# Bottom_rev1.net
KiCad netlist of a schematic drawn in EAGLE
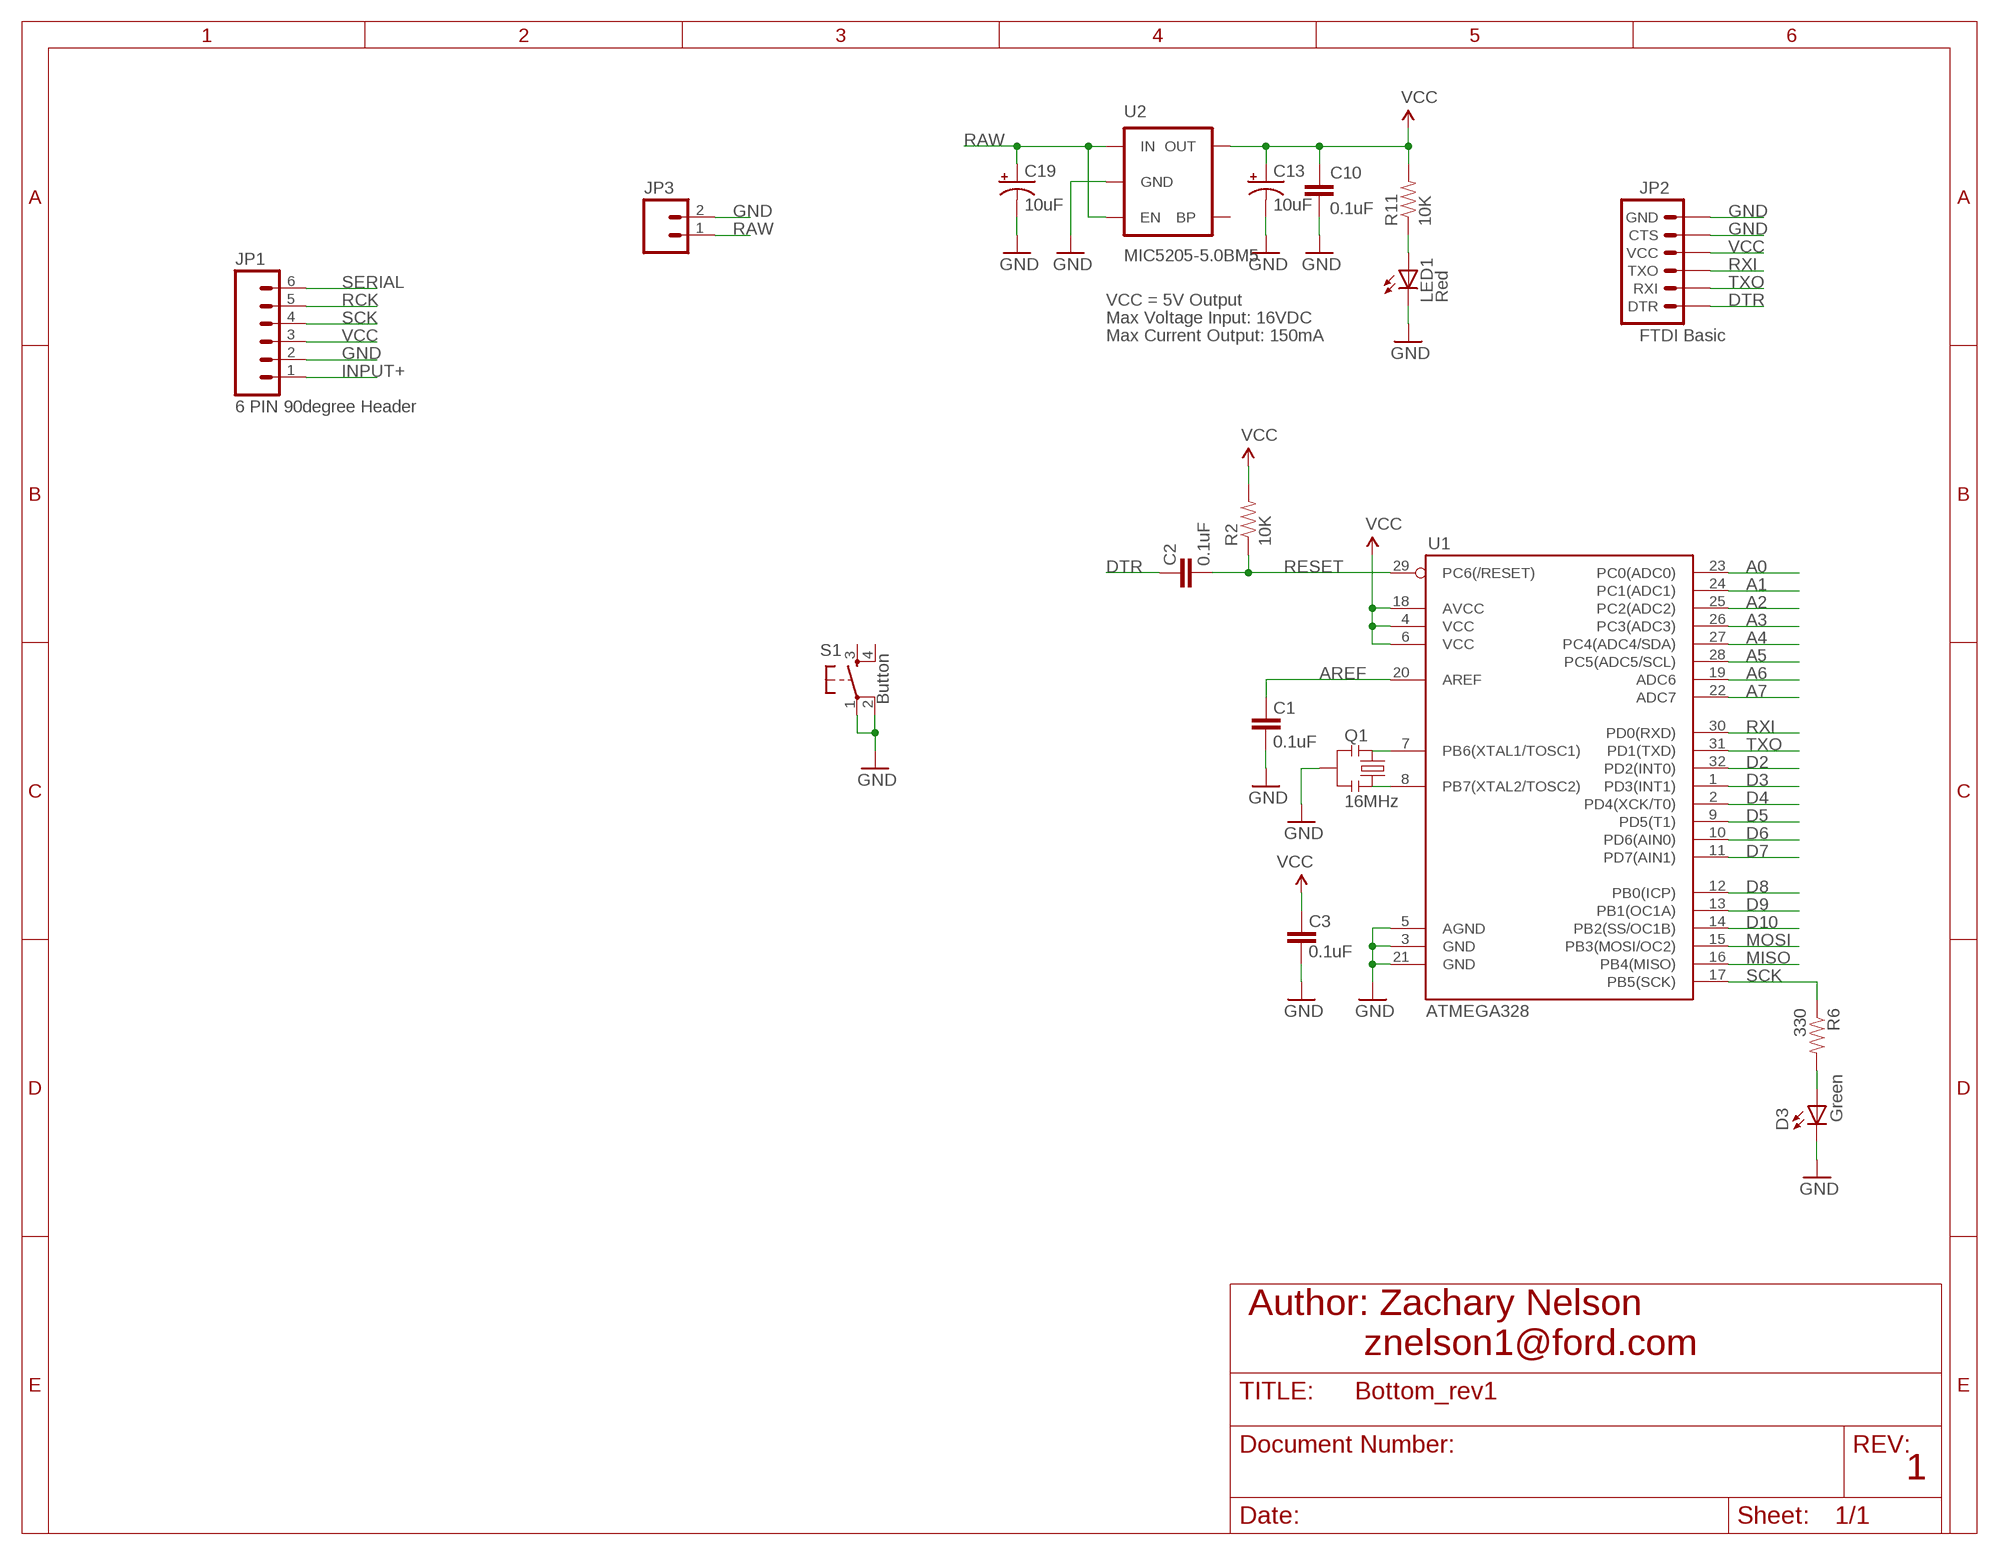
[diagram p0: schematic, sheet 1, part 1 of 2]
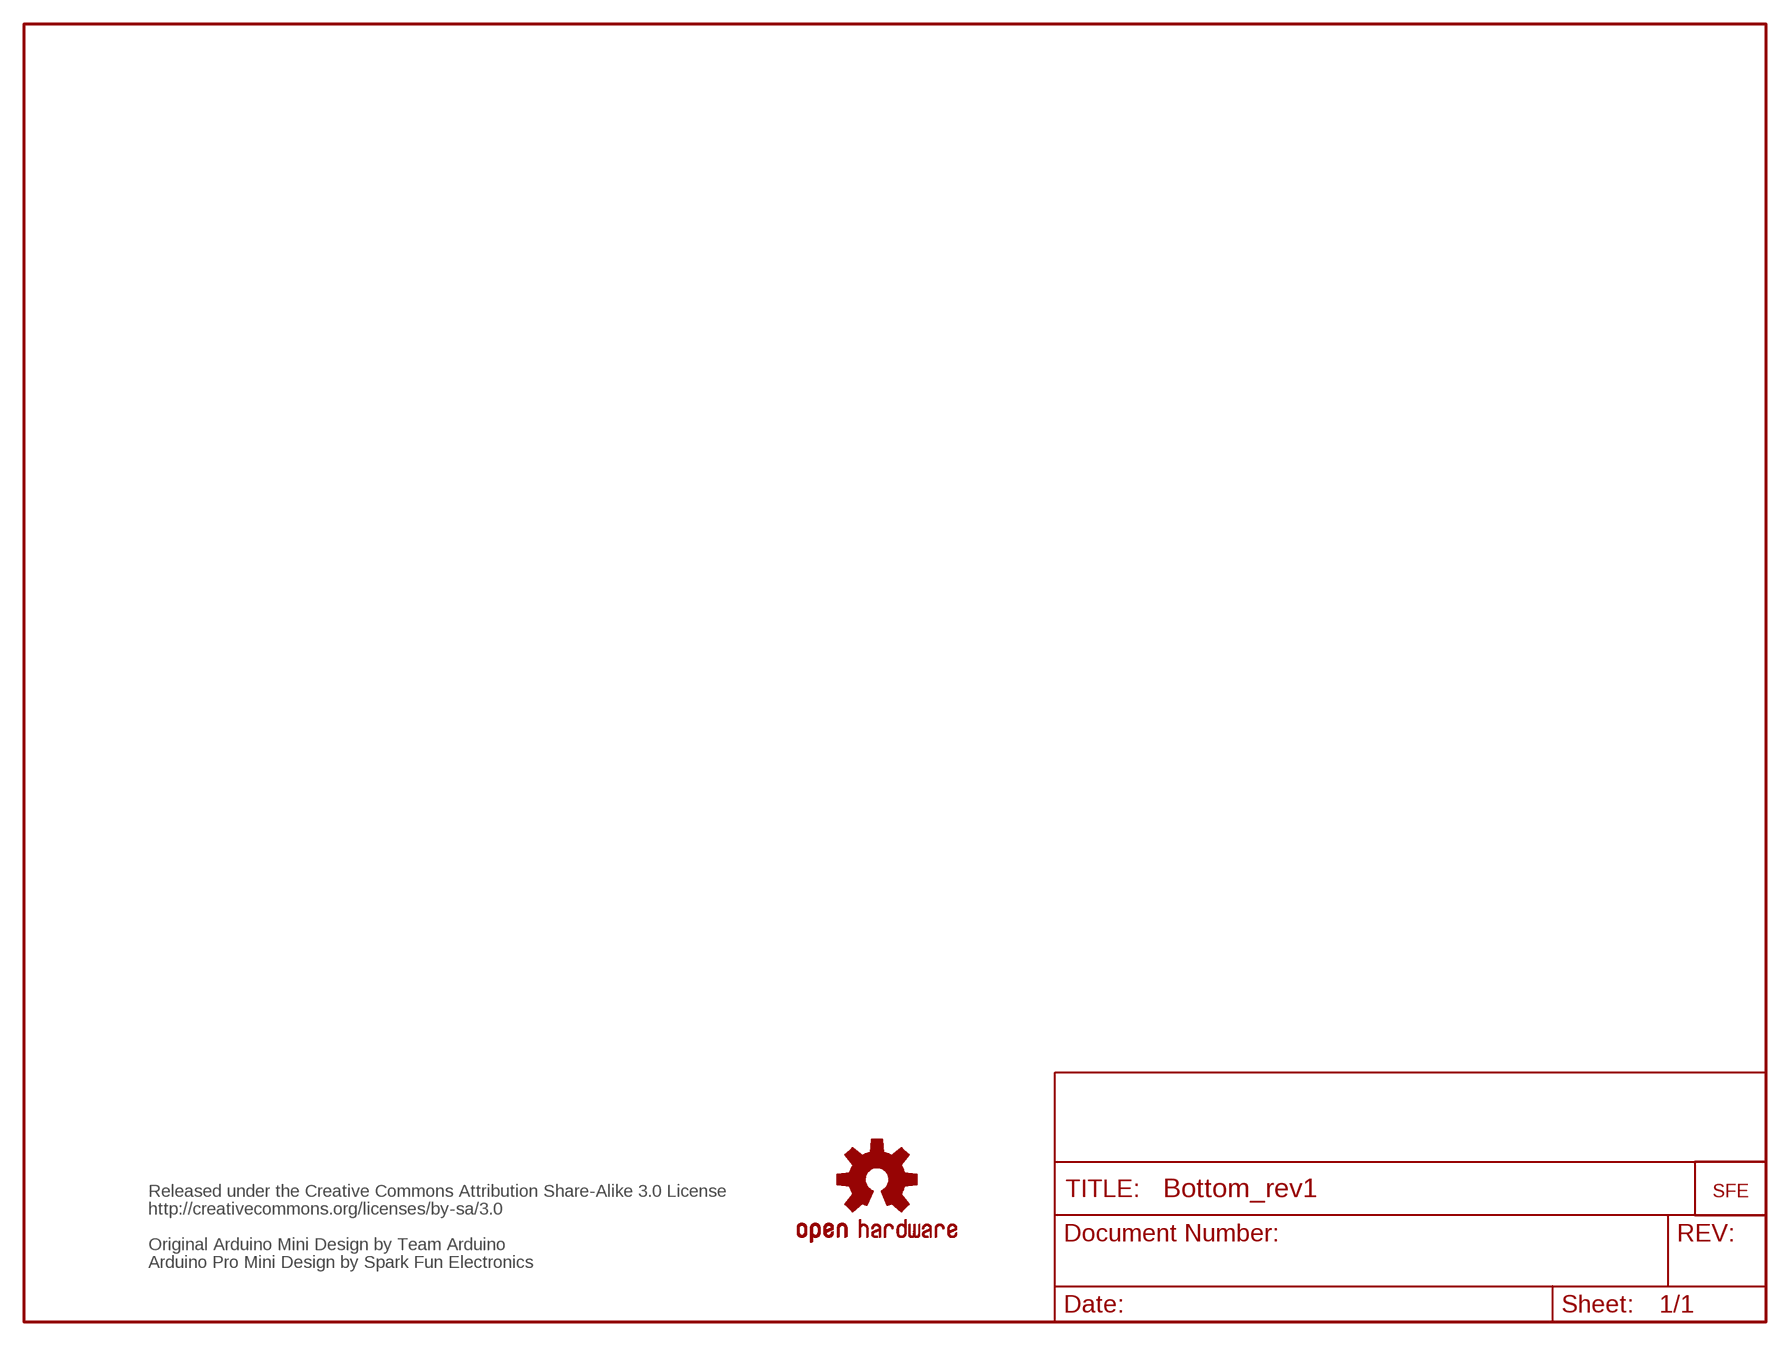
[diagram p1: schematic, sheet 1, part 2 of 2]

(export (version "E")
  (design (tool "Eeschema 10.0.6"))
  (components
    (comp (ref "C1")
      (value "0.1uF")
      (footprint "eagle-import:0402-CAP")
      (libsource (lib "eagle-import") (part "CAP0402-CAP"))
    )
    (comp (ref "C2")
      (value "0.1uF")
      (footprint "eagle-import:0402-CAP")
      (libsource (lib "eagle-import") (part "CAP0402-CAP"))
    )
    (comp (ref "C3")
      (value "0.1uF")
      (footprint "eagle-import:0402-CAP")
      (libsource (lib "eagle-import") (part "CAP0402-CAP"))
    )
    (comp (ref "C10")
      (value "0.1uF")
      (footprint "eagle-import:0402-CAP")
      (libsource (lib "eagle-import") (part "CAP0402-CAP"))
    )
    (comp (ref "C13")
      (value "10uF")
      (footprint "eagle-import:EIA3216")
      (libsource (lib "eagle-import") (part "CAP_POL1206"))
    )
    (comp (ref "C19")
      (value "10uF")
      (footprint "eagle-import:EIA3216")
      (libsource (lib "eagle-import") (part "CAP_POL1206"))
    )
    (comp (ref "D3")
      (value "Green")
      (footprint "eagle-import:LED-0603")
      (libsource (lib "eagle-import") (part "LED0603"))
    )
    (comp (ref "JP1")
      (value "6 PIN 90degree Header")
      (footprint "eagle-import:1X06_HOLES_ONLY")
      (libsource (lib "eagle-import") (part "M06POGOPIN_HOLES_ONLY"))
    )
    (comp (ref "JP2")
      (value "FTDI Basic")
      (footprint "eagle-import:1X06")
      (libsource (lib "eagle-import") (part "ARDUINO_SERIAL_PROGRAMPTH"))
    )
    (comp (ref "JP3")
      (value "M02POLAR")
      (footprint "eagle-import:MOLEX-1X2")
      (libsource (lib "eagle-import") (part "M02POLAR"))
    )
    (comp (ref "LED1")
      (value "Red")
      (footprint "eagle-import:LED-0603")
      (libsource (lib "eagle-import") (part "LED0603"))
    )
    (comp (ref "Q1")
      (value "16MHz")
      (footprint "eagle-import:RESONATOR-SMD")
      (libsource (lib "eagle-import") (part "RESONATORSMD"))
    )
    (comp (ref "R2")
      (value "10K")
      (footprint "eagle-import:0402-RES")
      (libsource (lib "eagle-import") (part "RESISTOR0402-RES"))
    )
    (comp (ref "R6")
      (value "330")
      (footprint "eagle-import:0402-RES")
      (libsource (lib "eagle-import") (part "RESISTOR0402-RES"))
    )
    (comp (ref "R11")
      (value "10K")
      (footprint "eagle-import:0402-RES")
      (libsource (lib "eagle-import") (part "RESISTOR0402-RES"))
    )
    (comp (ref "S1")
      (value "Button")
      (footprint "eagle-import:TACTILE_SWITCH_SMD")
      (libsource (lib "eagle-import") (part "TAC_SWITCHSMD"))
    )
    (comp (ref "U$3")
      (value "OSHW-LOGOS")
      (footprint "eagle-import:OSHW-LOGO-S")
      (libsource (lib "eagle-import") (part "OSHW-LOGOS"))
    )
    (comp (ref "U$11")
      (value "LOGO-SFENEW")
      (footprint "eagle-import:SFE-NEW-WEBLOGO")
      (libsource (lib "eagle-import") (part "LOGO-SFENEW"))
    )
    (comp (ref "U1")
      (value "ATMEGA328")
      (footprint "eagle-import:TQFP32-08")
      (libsource (lib "eagle-import") (part "ATMEGA168"))
    )
    (comp (ref "U2")
      (value "MIC5205-5.0BM5")
      (footprint "eagle-import:SOT23-5")
      (libsource (lib "eagle-import") (part "V_REG_LDOSMD"))
    )
  )
  (nets
    (net (code "1") (name "/A0") (class "Default")
      (node (ref "U1") (pin "23") (pinfunction "PC0(ADC0)_23") (pintype "bidirectional"))
    )
    (net (code "2") (name "/A1") (class "Default")
      (node (ref "U1") (pin "24") (pinfunction "PC1(ADC1)_24") (pintype "bidirectional"))
    )
    (net (code "3") (name "/A2") (class "Default")
      (node (ref "U1") (pin "25") (pinfunction "PC2(ADC2)_25") (pintype "bidirectional"))
    )
    (net (code "4") (name "/A3") (class "Default")
      (node (ref "U1") (pin "26") (pinfunction "PC3(ADC3)_26") (pintype "bidirectional"))
    )
    (net (code "5") (name "/A4") (class "Default")
      (node (ref "U1") (pin "27") (pinfunction "PC4(ADC4/SDA)_27") (pintype "bidirectional"))
    )
    (net (code "6") (name "/A5") (class "Default")
      (node (ref "U1") (pin "28") (pinfunction "PC5(ADC5/SCL)_28") (pintype "bidirectional"))
    )
    (net (code "7") (name "/A6") (class "Default")
      (node (ref "U1") (pin "19") (pinfunction "ADC6_19") (pintype "bidirectional"))
    )
    (net (code "8") (name "/A7") (class "Default")
      (node (ref "U1") (pin "22") (pinfunction "ADC7_22") (pintype "bidirectional"))
    )
    (net (code "9") (name "/AREF") (class "Default")
      (node (ref "C1") (pin "2") (pinfunction "2_2") (pintype "passive"))
      (node (ref "U1") (pin "20") (pinfunction "AREF_20") (pintype "bidirectional"))
    )
    (net (code "10") (name "/D2") (class "Default")
      (node (ref "U1") (pin "32") (pinfunction "PD2(INT0)_32") (pintype "bidirectional"))
    )
    (net (code "11") (name "/D3") (class "Default")
      (node (ref "U1") (pin "1") (pinfunction "PD3(INT1)_1") (pintype "bidirectional"))
    )
    (net (code "12") (name "/D4") (class "Default")
      (node (ref "U1") (pin "2") (pinfunction "PD4(XCK/T0)_2") (pintype "bidirectional"))
    )
    (net (code "13") (name "/D5") (class "Default")
      (node (ref "U1") (pin "9") (pinfunction "PD5(T1)_9") (pintype "bidirectional"))
    )
    (net (code "14") (name "/D6") (class "Default")
      (node (ref "U1") (pin "10") (pinfunction "PD6(AIN0)_10") (pintype "bidirectional"))
    )
    (net (code "15") (name "/D7") (class "Default")
      (node (ref "U1") (pin "11") (pinfunction "PD7(AIN1)_11") (pintype "bidirectional"))
    )
    (net (code "16") (name "/D8") (class "Default")
      (node (ref "U1") (pin "12") (pinfunction "PB0(ICP)_12") (pintype "bidirectional"))
    )
    (net (code "17") (name "/D9") (class "Default")
      (node (ref "U1") (pin "13") (pinfunction "PB1(OC1A)_13") (pintype "bidirectional"))
    )
    (net (code "18") (name "/D10") (class "Default")
      (node (ref "U1") (pin "14") (pinfunction "PB2(SS/OC1B)_14") (pintype "bidirectional"))
    )
    (net (code "19") (name "/DTR") (class "Default")
      (node (ref "C2") (pin "2") (pinfunction "2_2") (pintype "passive"))
      (node (ref "JP2") (pin "1") (pinfunction "DTR_1") (pintype "passive"))
    )
    (net (code "20") (name "/INPUT+") (class "Default")
      (node (ref "JP1") (pin "1") (pinfunction "1_1") (pintype "passive"))
    )
    (net (code "21") (name "/MISO") (class "Default")
      (node (ref "U1") (pin "16") (pinfunction "PB4(MISO)_16") (pintype "bidirectional"))
    )
    (net (code "22") (name "/MOSI") (class "Default")
      (node (ref "U1") (pin "15") (pinfunction "PB3(MOSI/OC2)_15") (pintype "bidirectional"))
    )
    (net (code "23") (name "/RAW") (class "Default")
      (node (ref "C19") (pin "A") (pinfunction "+_A") (pintype "passive"))
      (node (ref "JP3") (pin "1") (pinfunction "1_1") (pintype "passive"))
      (node (ref "U2") (pin "1") (pinfunction "IN_1") (pintype "input"))
      (node (ref "U2") (pin "3") (pinfunction "EN_3") (pintype "input"))
    )
    (net (code "24") (name "/RCK") (class "Default")
      (node (ref "JP1") (pin "5") (pinfunction "5_5") (pintype "passive"))
    )
    (net (code "25") (name "/RESET") (class "Default")
      (node (ref "C2") (pin "1") (pinfunction "1_1") (pintype "passive"))
      (node (ref "R2") (pin "1") (pinfunction "1_1") (pintype "passive"))
      (node (ref "U1") (pin "29") (pinfunction "PC6(/RESET)_29") (pintype "bidirectional"))
    )
    (net (code "26") (name "/RXI") (class "Default")
      (node (ref "JP2") (pin "3") (pinfunction "TXO_3") (pintype "passive"))
      (node (ref "U1") (pin "30") (pinfunction "PD0(RXD)_30") (pintype "bidirectional"))
    )
    (net (code "27") (name "/SCK") (class "Default")
      (node (ref "JP1") (pin "4") (pinfunction "4_4") (pintype "passive"))
      (node (ref "R6") (pin "1") (pinfunction "1_1") (pintype "passive"))
      (node (ref "U1") (pin "17") (pinfunction "PB5(SCK)_17") (pintype "bidirectional"))
    )
    (net (code "28") (name "/SERIAL") (class "Default")
      (node (ref "JP1") (pin "6") (pinfunction "6_6") (pintype "passive"))
    )
    (net (code "29") (name "/TXO") (class "Default")
      (node (ref "JP2") (pin "2") (pinfunction "RXI_2") (pintype "passive"))
      (node (ref "U1") (pin "31") (pinfunction "PD1(TXD)_31") (pintype "bidirectional"))
    )
    (net (code "30") (name "GND") (class "Default")
      (node (ref "C1") (pin "1") (pinfunction "1_1") (pintype "passive"))
      (node (ref "C10") (pin "2") (pinfunction "2_2") (pintype "passive"))
      (node (ref "C13") (pin "C") (pinfunction "-_C") (pintype "passive"))
      (node (ref "C19") (pin "C") (pinfunction "-_C") (pintype "passive"))
      (node (ref "C3") (pin "1") (pinfunction "1_1") (pintype "passive"))
      (node (ref "D3") (pin "C") (pinfunction "C_C") (pintype "passive"))
      (node (ref "JP1") (pin "2") (pinfunction "2_2") (pintype "passive"))
      (node (ref "JP2") (pin "5") (pinfunction "CTS_5") (pintype "passive"))
      (node (ref "JP2") (pin "6") (pinfunction "GND_6") (pintype "passive"))
      (node (ref "JP3") (pin "2") (pinfunction "2_2") (pintype "passive"))
      (node (ref "LED1") (pin "C") (pinfunction "C_C") (pintype "passive"))
      (node (ref "Q1") (pin "2") (pinfunction "2_2") (pintype "passive"))
      (node (ref "S1") (pin "1") (pinfunction "1_1") (pintype "passive"))
      (node (ref "S1") (pin "2") (pinfunction "2_2") (pintype "passive"))
      (node (ref "U1") (pin "21") (pinfunction "GND_21") (pintype "bidirectional"))
      (node (ref "U1") (pin "3") (pinfunction "GND_3") (pintype "bidirectional"))
      (node (ref "U1") (pin "5") (pinfunction "AGND_5") (pintype "bidirectional"))
      (node (ref "U2") (pin "2") (pinfunction "GND_2") (pintype "input"))
    )
    (net (code "31") (name "Net-(D3-PadA)") (class "Default")
      (node (ref "D3") (pin "A") (pinfunction "A_A") (pintype "passive"))
      (node (ref "R6") (pin "2") (pinfunction "2_2") (pintype "passive"))
    )
    (net (code "32") (name "Net-(LED1-PadA)") (class "Default")
      (node (ref "LED1") (pin "A") (pinfunction "A_A") (pintype "passive"))
      (node (ref "R11") (pin "1") (pinfunction "1_1") (pintype "passive"))
    )
    (net (code "33") (name "Net-(U1-PB6(XTAL1{slash}TOSC1))") (class "Default")
      (node (ref "Q1") (pin "3") (pinfunction "3_3") (pintype "passive"))
      (node (ref "U1") (pin "7") (pinfunction "PB6(XTAL1/TOSC1)_7") (pintype "bidirectional"))
    )
    (net (code "34") (name "Net-(U1-PB7(XTAL2{slash}TOSC2))") (class "Default")
      (node (ref "Q1") (pin "1") (pinfunction "1_1") (pintype "passive"))
      (node (ref "U1") (pin "8") (pinfunction "PB7(XTAL2/TOSC2)_8") (pintype "bidirectional"))
    )
    (net (code "35") (name "VCC") (class "Default")
      (node (ref "C10") (pin "1") (pinfunction "1_1") (pintype "passive"))
      (node (ref "C13") (pin "A") (pinfunction "+_A") (pintype "passive"))
      (node (ref "C3") (pin "2") (pinfunction "2_2") (pintype "passive"))
      (node (ref "JP1") (pin "3") (pinfunction "3_3") (pintype "passive"))
      (node (ref "JP2") (pin "4") (pinfunction "VCC_4") (pintype "passive"))
      (node (ref "R11") (pin "2") (pinfunction "2_2") (pintype "passive"))
      (node (ref "R2") (pin "2") (pinfunction "2_2") (pintype "passive"))
      (node (ref "U1") (pin "18") (pinfunction "AVCC_18") (pintype "bidirectional"))
      (node (ref "U1") (pin "4") (pinfunction "VCC_4") (pintype "bidirectional"))
      (node (ref "U1") (pin "6") (pinfunction "VCC_6") (pintype "bidirectional"))
      (node (ref "U2") (pin "5") (pinfunction "OUT_5") (pintype "passive"))
    )
    (net (code "36") (name "unconnected-(S1-Pad3)") (class "Default")
      (node (ref "S1") (pin "3") (pinfunction "3_3") (pintype "passive"))
    )
    (net (code "37") (name "unconnected-(S1-Pad4)") (class "Default")
      (node (ref "S1") (pin "4") (pinfunction "4_4") (pintype "passive"))
    )
    (net (code "38") (name "unconnected-(U2-BP-Pad4)") (class "Default")
      (node (ref "U2") (pin "4") (pinfunction "BP_4") (pintype "input"))
    )
  )
)
